# TXS0108_Breakout.net
KiCad netlist of a schematic drawn in EAGLE
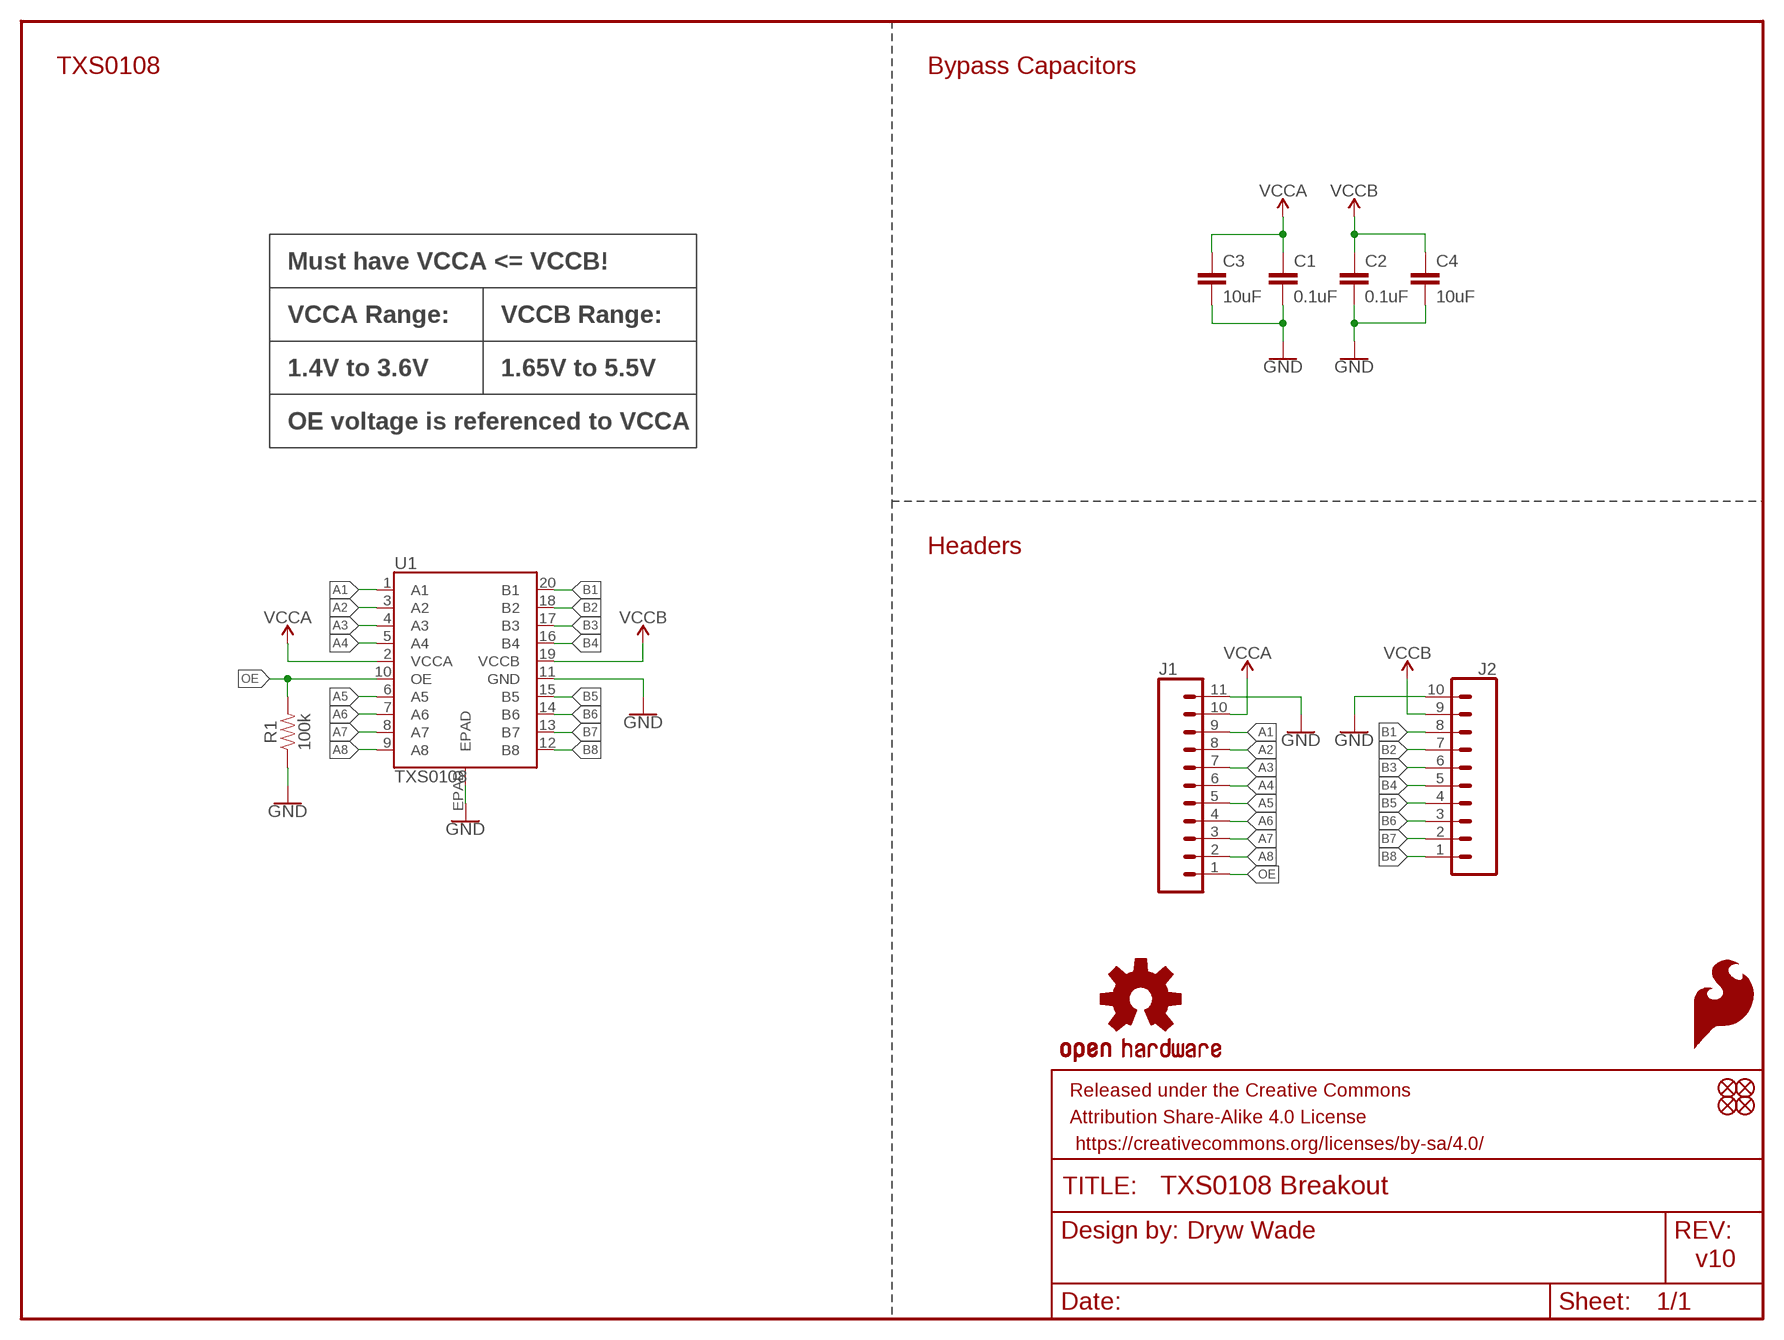
[diagram p0: schematic, sheet 1]

(export (version "E")
  (design (tool "Eeschema 10.0.6"))
  (components
    (comp (ref "C1")
      (value "0.1uF")
      (footprint "eagle-import:0603")
      (libsource (lib "eagle-import") (part "0.1UF-0603-25V-(+80/-20%)"))
    )
    (comp (ref "C2")
      (value "0.1uF")
      (footprint "eagle-import:0603")
      (libsource (lib "eagle-import") (part "0.1UF-0603-25V-(+80/-20%)"))
    )
    (comp (ref "C3")
      (value "10uF")
      (footprint "eagle-import:0603")
      (libsource (lib "eagle-import") (part "10UF-0603-6.3V-20%"))
    )
    (comp (ref "C4")
      (value "10uF")
      (footprint "eagle-import:0603")
      (libsource (lib "eagle-import") (part "10UF-0603-6.3V-20%"))
    )
    (comp (ref "FD1")
      (value "FIDUCIAL1X2")
      (footprint "eagle-import:FIDUCIAL-1X2")
      (libsource (lib "eagle-import") (part "FIDUCIAL1X2"))
    )
    (comp (ref "FD2")
      (value "FIDUCIAL1X2")
      (footprint "eagle-import:FIDUCIAL-1X2")
      (libsource (lib "eagle-import") (part "FIDUCIAL1X2"))
    )
    (comp (ref "FD3")
      (value "FIDUCIAL1X2")
      (footprint "eagle-import:FIDUCIAL-1X2")
      (libsource (lib "eagle-import") (part "FIDUCIAL1X2"))
    )
    (comp (ref "FD4")
      (value "FIDUCIAL1X2")
      (footprint "eagle-import:FIDUCIAL-1X2")
      (libsource (lib "eagle-import") (part "FIDUCIAL1X2"))
    )
    (comp (ref "FRAME1")
      (value "FRAME-LETTER")
      (footprint "eagle-import:CREATIVE_COMMONS")
      (libsource (lib "eagle-import") (part "FRAME-LETTER"))
    )
    (comp (ref "J1")
      (value "CONN_111X11_NO_SILK")
      (footprint "eagle-import:1X11_NO_SILK")
      (libsource (lib "eagle-import") (part "CONN_111X11_NO_SILK"))
    )
    (comp (ref "J2")
      (value "CONN_10NO_SILK_PTH_FEMALE")
      (footprint "eagle-import:1X10_NO_SILK")
      (libsource (lib "eagle-import") (part "CONN_10NO_SILK_PTH_FEMALE"))
    )
    (comp (ref "LOGO1")
      (value "OSHW-LOGOS")
      (footprint "eagle-import:OSHW-LOGO-S")
      (libsource (lib "eagle-import") (part "OSHW-LOGOS"))
    )
    (comp (ref "LOGO2")
      (value "SFE_LOGO_FLAME.1_INCH")
      (footprint "eagle-import:SFE_LOGO_FLAME_.1")
      (libsource (lib "eagle-import") (part "SFE_LOGO_FLAME.1_INCH"))
    )
    (comp (ref "R1")
      (value "100k")
      (footprint "eagle-import:0603")
      (libsource (lib "eagle-import") (part "100KOHM-0603-1/10W-1%"))
    )
    (comp (ref "U1")
      (value "TXS0108")
      (footprint "eagle-import:VFQFN-20")
      (libsource (lib "eagle-import") (part "TXS0108-VFQFN_20"))
    )
  )
  (nets
    (net (code "1") (name "A1") (class "Default")
      (node (ref "J1") (pin "9") (pinfunction "9_9") (pintype "passive"))
      (node (ref "U1") (pin "1") (pinfunction "A1_1") (pintype "bidirectional"))
    )
    (net (code "2") (name "A2") (class "Default")
      (node (ref "J1") (pin "8") (pinfunction "8_8") (pintype "passive"))
      (node (ref "U1") (pin "3") (pinfunction "A2_3") (pintype "bidirectional"))
    )
    (net (code "3") (name "A3") (class "Default")
      (node (ref "J1") (pin "7") (pinfunction "7_7") (pintype "passive"))
      (node (ref "U1") (pin "4") (pinfunction "A3_4") (pintype "bidirectional"))
    )
    (net (code "4") (name "A4") (class "Default")
      (node (ref "J1") (pin "6") (pinfunction "6_6") (pintype "passive"))
      (node (ref "U1") (pin "5") (pinfunction "A4_5") (pintype "bidirectional"))
    )
    (net (code "5") (name "A5") (class "Default")
      (node (ref "J1") (pin "5") (pinfunction "5_5") (pintype "passive"))
      (node (ref "U1") (pin "6") (pinfunction "A5_6") (pintype "bidirectional"))
    )
    (net (code "6") (name "A6") (class "Default")
      (node (ref "J1") (pin "4") (pinfunction "4_4") (pintype "passive"))
      (node (ref "U1") (pin "7") (pinfunction "A6_7") (pintype "bidirectional"))
    )
    (net (code "7") (name "A7") (class "Default")
      (node (ref "J1") (pin "3") (pinfunction "3_3") (pintype "passive"))
      (node (ref "U1") (pin "8") (pinfunction "A7_8") (pintype "bidirectional"))
    )
    (net (code "8") (name "A8") (class "Default")
      (node (ref "J1") (pin "2") (pinfunction "2_2") (pintype "passive"))
      (node (ref "U1") (pin "9") (pinfunction "A8_9") (pintype "bidirectional"))
    )
    (net (code "9") (name "B1") (class "Default")
      (node (ref "J2") (pin "8") (pinfunction "8_8") (pintype "passive"))
      (node (ref "U1") (pin "20") (pinfunction "B1_20") (pintype "bidirectional"))
    )
    (net (code "10") (name "B2") (class "Default")
      (node (ref "J2") (pin "7") (pinfunction "7_7") (pintype "passive"))
      (node (ref "U1") (pin "18") (pinfunction "B2_18") (pintype "bidirectional"))
    )
    (net (code "11") (name "B3") (class "Default")
      (node (ref "J2") (pin "6") (pinfunction "6_6") (pintype "passive"))
      (node (ref "U1") (pin "17") (pinfunction "B3_17") (pintype "bidirectional"))
    )
    (net (code "12") (name "B4") (class "Default")
      (node (ref "J2") (pin "5") (pinfunction "5_5") (pintype "passive"))
      (node (ref "U1") (pin "16") (pinfunction "B4_16") (pintype "bidirectional"))
    )
    (net (code "13") (name "B5") (class "Default")
      (node (ref "J2") (pin "4") (pinfunction "4_4") (pintype "passive"))
      (node (ref "U1") (pin "15") (pinfunction "B5_15") (pintype "bidirectional"))
    )
    (net (code "14") (name "B6") (class "Default")
      (node (ref "J2") (pin "3") (pinfunction "3_3") (pintype "passive"))
      (node (ref "U1") (pin "14") (pinfunction "B6_14") (pintype "bidirectional"))
    )
    (net (code "15") (name "B7") (class "Default")
      (node (ref "J2") (pin "2") (pinfunction "2_2") (pintype "passive"))
      (node (ref "U1") (pin "13") (pinfunction "B7_13") (pintype "bidirectional"))
    )
    (net (code "16") (name "B8") (class "Default")
      (node (ref "J2") (pin "1") (pinfunction "1_1") (pintype "passive"))
      (node (ref "U1") (pin "12") (pinfunction "B8_12") (pintype "bidirectional"))
    )
    (net (code "17") (name "GND") (class "Default")
      (node (ref "C1") (pin "2") (pinfunction "2_2") (pintype "passive"))
      (node (ref "C2") (pin "2") (pinfunction "2_2") (pintype "passive"))
      (node (ref "C3") (pin "2") (pinfunction "2_2") (pintype "passive"))
      (node (ref "C4") (pin "2") (pinfunction "2_2") (pintype "passive"))
      (node (ref "J1") (pin "11") (pinfunction "11_11") (pintype "passive"))
      (node (ref "J2") (pin "10") (pinfunction "10_10") (pintype "passive"))
      (node (ref "R1") (pin "1") (pinfunction "1_1") (pintype "passive"))
      (node (ref "U1") (pin "11") (pinfunction "GND_11") (pintype "bidirectional"))
      (node (ref "U1") (pin "EPAD") (pinfunction "EPAD_EPAD") (pintype "bidirectional"))
    )
    (net (code "18") (name "OE") (class "Default")
      (node (ref "J1") (pin "1") (pinfunction "1_1") (pintype "passive"))
      (node (ref "R1") (pin "2") (pinfunction "2_2") (pintype "passive"))
      (node (ref "U1") (pin "10") (pinfunction "OE_10") (pintype "bidirectional"))
    )
    (net (code "19") (name "VCCA") (class "Default")
      (node (ref "C1") (pin "1") (pinfunction "1_1") (pintype "passive"))
      (node (ref "C3") (pin "1") (pinfunction "1_1") (pintype "passive"))
      (node (ref "J1") (pin "10") (pinfunction "10_10") (pintype "passive"))
      (node (ref "U1") (pin "2") (pinfunction "VCCA_2") (pintype "bidirectional"))
    )
    (net (code "20") (name "VCCB") (class "Default")
      (node (ref "C2") (pin "1") (pinfunction "1_1") (pintype "passive"))
      (node (ref "C4") (pin "1") (pinfunction "1_1") (pintype "passive"))
      (node (ref "J2") (pin "9") (pinfunction "9_9") (pintype "passive"))
      (node (ref "U1") (pin "19") (pinfunction "VCCB_19") (pintype "bidirectional"))
    )
  )
)
